# PROC010C_SOP_Headers_Reference.net
KiCad netlist of a schematic drawn in Altium Designer
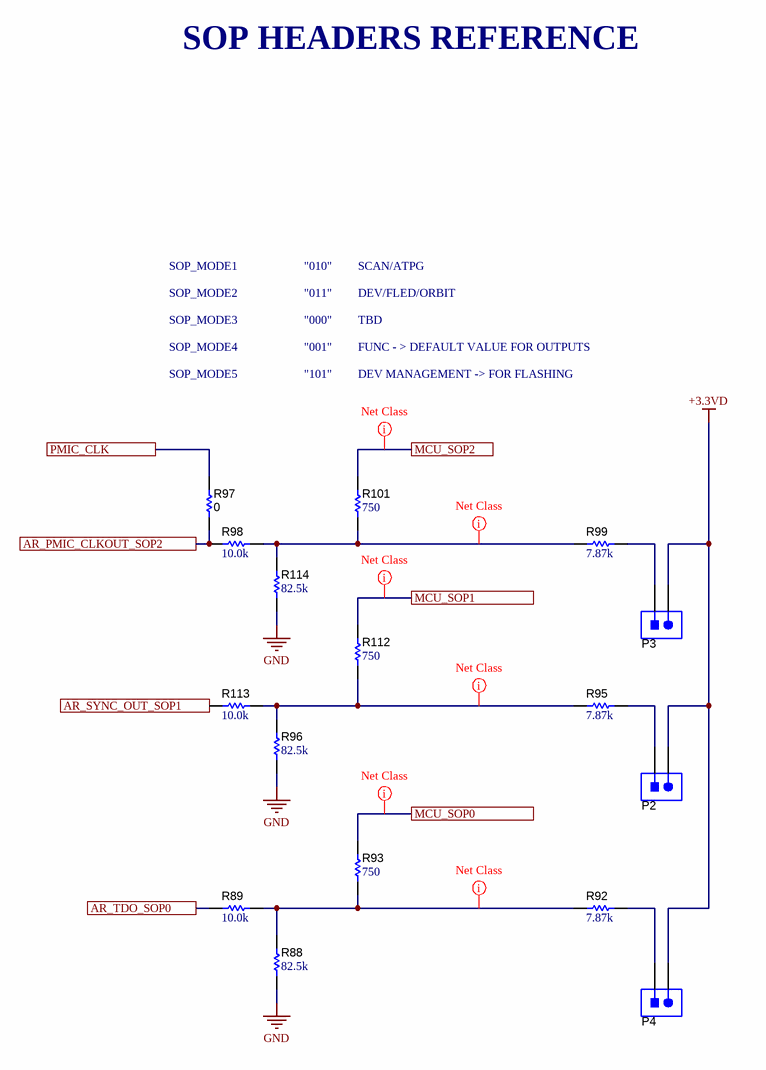
[diagram p0: PROC010C_SOP_Headers_Reference.SchDoc]

(export (version "E")
  (design (tool "Eeschema 10.0.6"))
  (components
    (comp (ref "P2")
      (value "TSW-102-07-G-S")
      (footprint "TSW-102-07-G-S")
      (description "Header, 100mil, 2x1, Gold, TH")
      (fields (field (name "MANUFACTURER") "Samtec"))
      (libsource (lib "Altium Vault - TI") (part "CMP-0075405-2"))
    )
    (comp (ref "P3")
      (value "TSW-102-07-G-S")
      (footprint "TSW-102-07-G-S")
      (description "Header, 100mil, 2x1, Gold, TH")
      (fields (field (name "MANUFACTURER") "Samtec"))
      (libsource (lib "Altium Vault - TI") (part "CMP-0075405-2"))
    )
    (comp (ref "P4")
      (value "TSW-102-07-G-S")
      (footprint "TSW-102-07-G-S")
      (description "Header, 100mil, 2x1, Gold, TH")
      (fields (field (name "MANUFACTURER") "Samtec"))
      (libsource (lib "Altium Vault - TI") (part "CMP-0075405-2"))
    )
    (comp (ref "R88")
      (value "CRCW040282K5FKED")
      (footprint "0402L")
      (description "RES, 82.5 k, 1%, 0.063 W, AEC-Q200 Grade 0, 0402")
      (fields (field (name "MANUFACTURER") "Vishay-Dale") (field (name "VALUEDISPLAYED") "82.5k"))
      (libsource (lib "Altium Vault - TI") (part "Resistor"))
    )
    (comp (ref "R89")
      (value "CRCW040210K0FKED")
      (footprint "0402L")
      (description "RES, 10.0 k, 1%, 0.063 W, AEC-Q200 Grade 0, 0402")
      (fields (field (name "MANUFACTURER") "Vishay-Dale") (field (name "VALUEDISPLAYED") "10.0k"))
      (libsource (lib "Altium Vault - TI") (part "CMP-0025958-3"))
    )
    (comp (ref "R92")
      (value "CRCW04027K87FKED")
      (footprint "0402L")
      (description "RES, 7.87 k, 1%, 0.063 W, AEC-Q200 Grade 0, 0402")
      (fields (field (name "MANUFACTURER") "Vishay-Dale") (field (name "VALUEDISPLAYED") "7.87k"))
      (libsource (lib "Altium Vault - TI") (part "Resistor"))
    )
    (comp (ref "R93")
      (value "CRCW0402750RFKED")
      (footprint "0402L")
      (description "RES, 750, 1%, 0.063 W, AEC-Q200 Grade 0, 0402")
      (fields (field (name "MANUFACTURER") "Vishay-Dale") (field (name "VALUEDISPLAYED") "750"))
      (libsource (lib "Altium Vault - TI") (part "Resistor"))
    )
    (comp (ref "R95")
      (value "CRCW04027K87FKED")
      (footprint "0402L")
      (description "RES, 7.87 k, 1%, 0.063 W, AEC-Q200 Grade 0, 0402")
      (fields (field (name "MANUFACTURER") "Vishay-Dale") (field (name "VALUEDISPLAYED") "7.87k"))
      (libsource (lib "Altium Vault - TI") (part "Resistor"))
    )
    (comp (ref "R96")
      (value "CRCW040282K5FKED")
      (footprint "0402L")
      (description "RES, 82.5 k, 1%, 0.063 W, AEC-Q200 Grade 0, 0402")
      (fields (field (name "MANUFACTURER") "Vishay-Dale") (field (name "VALUEDISPLAYED") "82.5k"))
      (libsource (lib "Altium Vault - TI") (part "Resistor"))
    )
    (comp (ref "R97")
      (value "ERJ-2GE0R00X")
      (footprint "0402L")
      (description "RES, 0, 5%, 0.063 W, 0402")
      (fields
        (field (name "MANUFACTURER") "Panasonic")
        (field (name "VALUEDISPLAYED") "0")
        (field (name "PUBLISHER") "Texas Instruments")
      )
      (libsource (lib "Altium Vault - TI") (part "CMP-0026992-2"))
    )
    (comp (ref "R98")
      (value "CRCW040210K0FKED")
      (footprint "0402L")
      (description "RES, 10.0 k, 1%, 0.063 W, AEC-Q200 Grade 0, 0402")
      (fields (field (name "MANUFACTURER") "Vishay-Dale") (field (name "VALUEDISPLAYED") "10.0k"))
      (libsource (lib "Altium Vault - TI") (part "CMP-0025958-3"))
    )
    (comp (ref "R99")
      (value "CRCW04027K87FKED")
      (footprint "0402L")
      (description "RES, 7.87 k, 1%, 0.063 W, AEC-Q200 Grade 0, 0402")
      (fields (field (name "MANUFACTURER") "Vishay-Dale") (field (name "VALUEDISPLAYED") "7.87k"))
      (libsource (lib "Altium Vault - TI") (part "Resistor"))
    )
    (comp (ref "R101")
      (value "CRCW0402750RFKED")
      (footprint "0402L")
      (description "RES, 750, 1%, 0.063 W, AEC-Q200 Grade 0, 0402")
      (fields (field (name "MANUFACTURER") "Vishay-Dale") (field (name "VALUEDISPLAYED") "750"))
      (libsource (lib "Altium Vault - TI") (part "CMP-0026542-2"))
    )
    (comp (ref "R112")
      (value "CRCW0402750RFKED")
      (footprint "0402L")
      (description "RES, 750, 1%, 0.063 W, AEC-Q200 Grade 0, 0402")
      (fields (field (name "MANUFACTURER") "Vishay-Dale") (field (name "VALUEDISPLAYED") "750"))
      (libsource (lib "Altium Vault - TI") (part "Resistor"))
    )
    (comp (ref "R113")
      (value "CRCW040210K0FKED")
      (footprint "0402L")
      (description "RES, 10.0 k, 1%, 0.063 W, AEC-Q200 Grade 0, 0402")
      (fields (field (name "MANUFACTURER") "Vishay-Dale") (field (name "VALUEDISPLAYED") "10.0k"))
      (libsource (lib "Altium Vault - TI") (part "CMP-0025958-3"))
    )
    (comp (ref "R114")
      (value "CRCW040282K5FKED")
      (footprint "0402L")
      (description "RES, 82.5 k, 1%, 0.063 W, AEC-Q200 Grade 0, 0402")
      (fields (field (name "MANUFACTURER") "Vishay-Dale") (field (name "VALUEDISPLAYED") "82.5k"))
      (libsource (lib "Altium Vault - TI") (part "CMP-0026574-2"))
    )
  )
  (nets
    (net (code "1") (name "+3.3VD") (class "Default")
      (node (ref "P2") (pin "2") (pinfunction "2_2") (pintype "passive"))
      (node (ref "P3") (pin "2") (pinfunction "2_2") (pintype "passive"))
      (node (ref "P4") (pin "2") (pinfunction "2_2") (pintype "passive"))
    )
    (net (code "2") (name "/AR_PMIC_CLKOUT_SOP2") (class "Default")
      (node (ref "R97") (pin "1") (pinfunction "1_1") (pintype "passive"))
      (node (ref "R98") (pin "1") (pinfunction "1_1") (pintype "passive"))
    )
    (net (code "3") (name "/AR_SYNC_OUT_SOP1") (class "Default")
      (node (ref "R113") (pin "1") (pinfunction "1_1") (pintype "passive"))
    )
    (net (code "4") (name "/AR_TDO_SOP0") (class "Default")
      (node (ref "R89") (pin "1") (pinfunction "1_1") (pintype "passive"))
    )
    (net (code "5") (name "/MCU_SOP0") (class "Default")
      (node (ref "R93") (pin "2") (pinfunction "2_2") (pintype "passive"))
    )
    (net (code "6") (name "/MCU_SOP1") (class "Default")
      (node (ref "R112") (pin "2") (pinfunction "2_2") (pintype "passive"))
    )
    (net (code "7") (name "/MCU_SOP2") (class "Default")
      (node (ref "R101") (pin "2") (pinfunction "2_2") (pintype "passive"))
    )
    (net (code "8") (name "/PMIC_CLK") (class "Default")
      (node (ref "R97") (pin "2") (pinfunction "2_2") (pintype "passive"))
    )
    (net (code "9") (name "GND") (class "Default")
      (node (ref "R114") (pin "1") (pinfunction "1_1") (pintype "passive"))
      (node (ref "R88") (pin "1") (pinfunction "1_1") (pintype "passive"))
      (node (ref "R96") (pin "1") (pinfunction "1_1") (pintype "passive"))
    )
    (net (code "10") (name "Net-(P2-Pad1)") (class "Default")
      (node (ref "P2") (pin "1") (pinfunction "1_1") (pintype "passive"))
      (node (ref "R95") (pin "2") (pinfunction "2_2") (pintype "passive"))
    )
    (net (code "11") (name "Net-(P3-Pad1)") (class "Default")
      (node (ref "P3") (pin "1") (pinfunction "1_1") (pintype "passive"))
      (node (ref "R99") (pin "2") (pinfunction "2_2") (pintype "passive"))
    )
    (net (code "12") (name "Net-(P4-Pad1)") (class "Default")
      (node (ref "P4") (pin "1") (pinfunction "1_1") (pintype "passive"))
      (node (ref "R92") (pin "2") (pinfunction "2_2") (pintype "passive"))
    )
    (net (code "13") (name "Net-(R88-Pad2)") (class "Default")
      (node (ref "R88") (pin "2") (pinfunction "2_2") (pintype "passive"))
      (node (ref "R89") (pin "2") (pinfunction "2_2") (pintype "passive"))
      (node (ref "R92") (pin "1") (pinfunction "1_1") (pintype "passive"))
      (node (ref "R93") (pin "1") (pinfunction "1_1") (pintype "passive"))
    )
    (net (code "14") (name "Net-(R101-Pad1)") (class "Default")
      (node (ref "R101") (pin "1") (pinfunction "1_1") (pintype "passive"))
      (node (ref "R114") (pin "2") (pinfunction "2_2") (pintype "passive"))
      (node (ref "R98") (pin "2") (pinfunction "2_2") (pintype "passive"))
      (node (ref "R99") (pin "1") (pinfunction "1_1") (pintype "passive"))
    )
    (net (code "15") (name "Net-(R112-Pad1)") (class "Default")
      (node (ref "R112") (pin "1") (pinfunction "1_1") (pintype "passive"))
      (node (ref "R113") (pin "2") (pinfunction "2_2") (pintype "passive"))
      (node (ref "R95") (pin "1") (pinfunction "1_1") (pintype "passive"))
      (node (ref "R96") (pin "2") (pinfunction "2_2") (pintype "passive"))
    )
  )
)
